# Sheet2.net
KiCad netlist of a schematic drawn in Altium Designer
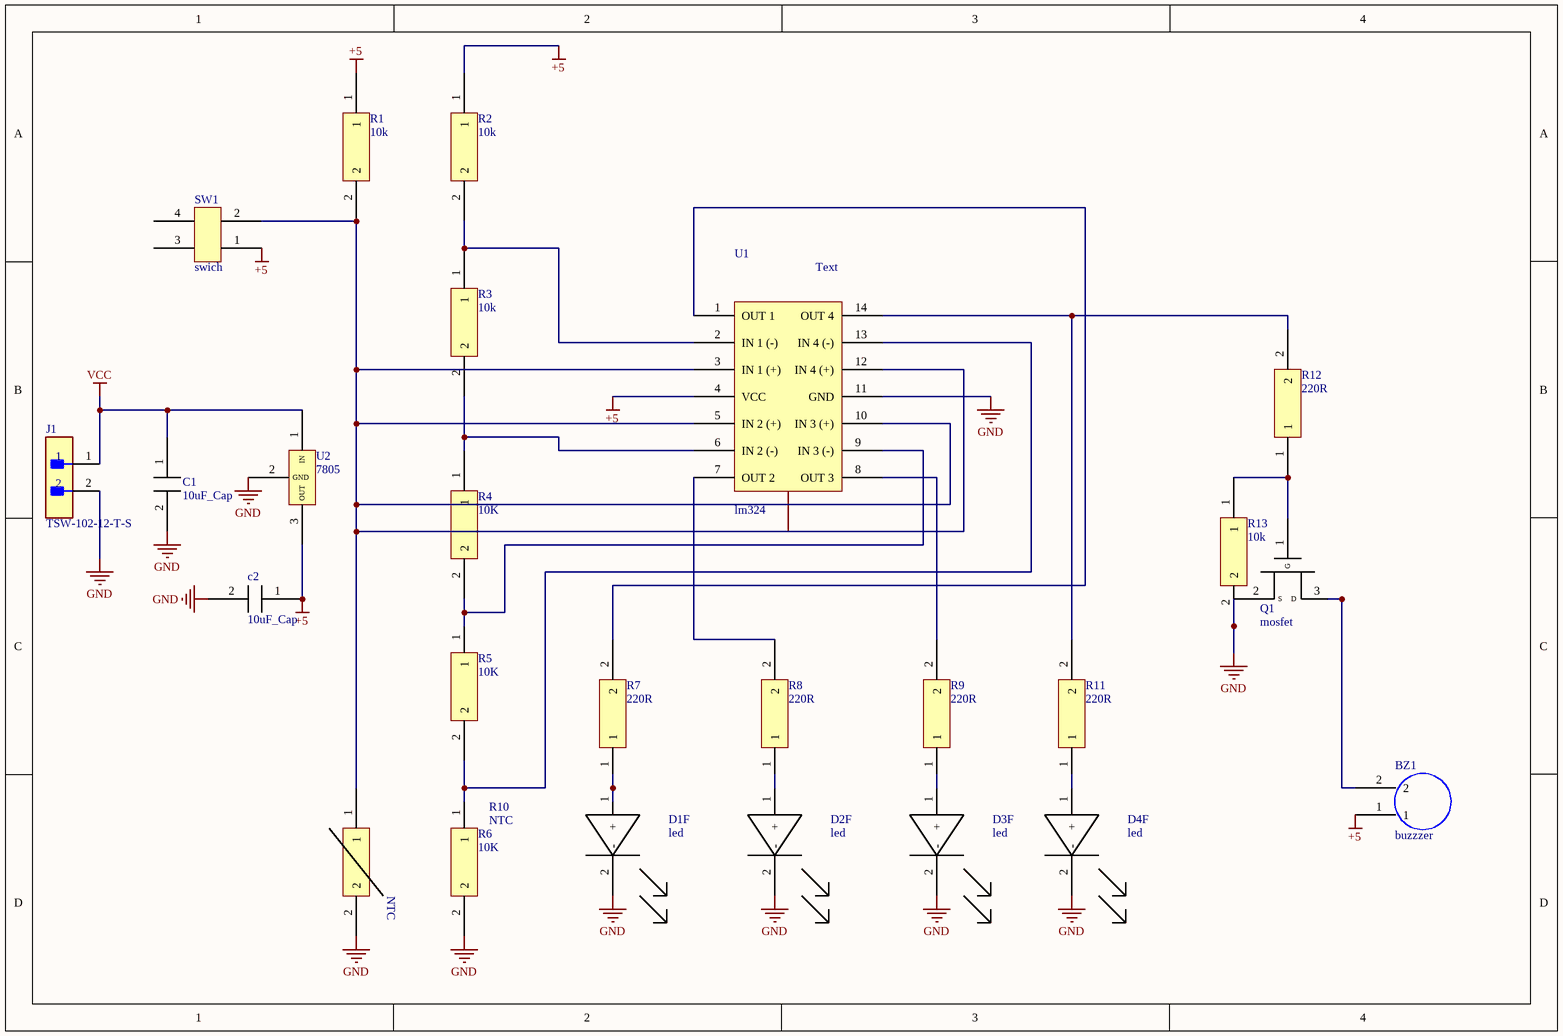
[diagram p0: Sheet2.SchDoc]

(export (version "E")
  (design (tool "Eeschema 10.0.6"))
  (components
    (comp (ref "BZ1")
      (value "buzzzer")
      (footprint "PCBComponent_1")
      (libsource (lib "Schlib1") (part "buzzzer"))
    )
    (comp (ref "C1")
      (value "10uF_Cap")
      (footprint "CAPCP2012X14N")
      (libsource (lib "Schlib1") (part "10uF_Cap"))
    )
    (comp (ref "c2")
      (value "10uF_Cap")
      (footprint "DIOC2012X06N")
      (libsource (lib "Schlib1") (part "10uF_Cap"))
    )
    (comp (ref "D1") (value "led") (footprint "DIOC2012X06") (libsource (lib "Schlib1") (part "led")))
    (comp (ref "D2") (value "led") (footprint "DIOC2012X06N") (libsource (lib "Schlib1") (part "led")))
    (comp (ref "D3") (value "led") (footprint "DIOC2012X06N") (libsource (lib "Schlib1") (part "led")))
    (comp (ref "D4") (value "led") (footprint "DIOC2012X06N") (libsource (lib "Schlib1") (part "led")))
    (comp (ref "J1")
      (value "TSW-102-12-T-S")
      (footprint "FP-TSW-102-12-T-S-MFG")
      (description "CONN HEADER VERT 2POS 2.54MM")
      (libsource (lib "Altium Content Vault") (part "3bc925449376181038e59eaffc5286c"))
    )
    (comp (ref "Q1")
      (value "mosfet")
      (footprint "SOT95P245X110-3N")
      (libsource (lib "Schlib1") (part "mosfet"))
    )
    (comp (ref "R1")
      (value "10k")
      (footprint "CAPCP2012X14N")
      (description "RES_0805")
      (libsource (lib "Schlib1") (part "RES_0805"))
    )
    (comp (ref "R2")
      (value "10k")
      (footprint "CAPCP2012X14N")
      (description "RES_0805")
      (libsource (lib "Schlib1") (part "RES_0805"))
    )
    (comp (ref "R3")
      (value "10k")
      (footprint "CAPCP2012X14N")
      (description "RES_0805")
      (libsource (lib "Schlib1") (part "RES_0805"))
    )
    (comp (ref "R4")
      (value "10K")
      (footprint "CAPCP2012X14N")
      (description "RES_0805")
      (libsource (lib "Schlib1") (part "RES_0805"))
    )
    (comp (ref "R5")
      (value "10K")
      (footprint "CAPCP2012X14N")
      (description "RES_0805")
      (libsource (lib "Schlib1") (part "RES_0805"))
    )
    (comp (ref "R6")
      (value "10K")
      (footprint "CAPCP2012X14N")
      (description "RES_0805")
      (libsource (lib "Schlib1") (part "RES_0805"))
    )
    (comp (ref "R7")
      (value "220R")
      (footprint "CAPCP2012X14N")
      (description "RES_0805")
      (libsource (lib "") (part "RES_0805_1"))
    )
    (comp (ref "R8")
      (value "220R")
      (footprint "CAPCP2012X14N")
      (description "RES_0805")
      (libsource (lib "") (part "RES_0805_1"))
    )
    (comp (ref "R9")
      (value "220R")
      (footprint "CAPCP2012X14N")
      (description "RES_0805")
      (libsource (lib "") (part "RES_0805_1"))
    )
    (comp (ref "R10") (value "NTC") (footprint "NTC") (libsource (lib "Schlib1") (part "NTC")))
    (comp (ref "R11")
      (value "220R")
      (footprint "CAPCP2012X14N")
      (description "RES_0805")
      (libsource (lib "") (part "RES_0805_1"))
    )
    (comp (ref "R12")
      (value "220R")
      (footprint "RESC2012X06N")
      (description "RES_0805")
      (libsource (lib "") (part "RES_0805_1"))
    )
    (comp (ref "R13")
      (value "10k")
      (footprint "RESC2012X06N")
      (description "RES_0805")
      (libsource (lib "Schlib1") (part "RES_0805"))
    )
    (comp (ref "SW1")
      (value "swich")
      (footprint "PCBComponent_1 - duplicate4")
      (libsource (lib "Schlib1") (part "swich"))
    )
    (comp (ref "U1")
      (value "lm324")
      (footprint "SOIC127P600X175-14N")
      (libsource (lib "Schlib1") (part "lm324"))
    )
    (comp (ref "U2")
      (value "7805")
      (footprint "DPAK228P990X238-3N")
      (libsource (lib "Schlib1") (part "7805"))
    )
  )
  (nets
    (net (code "1") (name "+5") (class "Default")
      (node (ref "BZ1") (pin "1") (pinfunction "1_1") (pintype "passive"))
      (node (ref "R1") (pin "1") (pinfunction "1_1") (pintype "passive"))
      (node (ref "R2") (pin "1") (pinfunction "1_1") (pintype "passive"))
      (node (ref "SW1") (pin "1") (pintype "passive"))
      (node (ref "U1") (pin "4") (pinfunction "VCC_4") (pintype "passive"))
      (node (ref "U2") (pin "3") (pinfunction "OUT_3") (pintype "passive"))
      (node (ref "c2") (pin "1") (pintype "passive"))
    )
    (net (code "2") (name "GND") (class "Default")
      (node (ref "C1") (pin "2") (pintype "passive"))
      (node (ref "D1") (pin "2") (pinfunction "-_2") (pintype "passive"))
      (node (ref "D2") (pin "2") (pinfunction "-_2") (pintype "passive"))
      (node (ref "D3") (pin "2") (pinfunction "-_2") (pintype "passive"))
      (node (ref "D4") (pin "2") (pinfunction "-_2") (pintype "passive"))
      (node (ref "J1") (pin "2") (pinfunction "2_2") (pintype "passive"))
      (node (ref "Q1") (pin "2") (pinfunction "S_2") (pintype "passive"))
      (node (ref "R10") (pin "2") (pinfunction "2_2") (pintype "passive"))
      (node (ref "R13") (pin "2") (pinfunction "2_2") (pintype "passive"))
      (node (ref "R6") (pin "2") (pinfunction "2_2") (pintype "passive"))
      (node (ref "U1") (pin "11") (pinfunction "GND_11") (pintype "passive"))
      (node (ref "U2") (pin "2") (pinfunction "GND_2") (pintype "passive"))
      (node (ref "c2") (pin "2") (pintype "passive"))
    )
    (net (code "3") (name "Net-(D1F-+)") (class "Default")
      (node (ref "D1") (pin "1") (pinfunction "+_1") (pintype "passive"))
      (node (ref "R7") (pin "1") (pinfunction "1_1") (pintype "passive"))
    )
    (net (code "4") (name "Net-(D2F-+)") (class "Default")
      (node (ref "D2") (pin "1") (pinfunction "+_1") (pintype "passive"))
      (node (ref "R8") (pin "1") (pinfunction "1_1") (pintype "passive"))
    )
    (net (code "5") (name "Net-(D3F-+)") (class "Default")
      (node (ref "D3") (pin "1") (pinfunction "+_1") (pintype "passive"))
      (node (ref "R9") (pin "1") (pinfunction "1_1") (pintype "passive"))
    )
    (net (code "6") (name "Net-(D4F-+)") (class "Default")
      (node (ref "D4") (pin "1") (pinfunction "+_1") (pintype "passive"))
      (node (ref "R11") (pin "1") (pinfunction "1_1") (pintype "passive"))
    )
    (net (code "7") (name "Net-(Q1-D)") (class "Default")
      (node (ref "BZ1") (pin "2") (pinfunction "2_2") (pintype "passive"))
      (node (ref "Q1") (pin "3") (pinfunction "D_3") (pintype "passive"))
    )
    (net (code "8") (name "Net-(Q1-G)") (class "Default")
      (node (ref "Q1") (pin "1") (pinfunction "G_1") (pintype "passive"))
      (node (ref "R12") (pin "1") (pinfunction "1_1") (pintype "passive"))
      (node (ref "R13") (pin "1") (pinfunction "1_1") (pintype "passive"))
    )
    (net (code "9") (name "Net-(U1-IN_1_(+))") (class "Default")
      (node (ref "R1") (pin "2") (pinfunction "2_2") (pintype "passive"))
      (node (ref "R10") (pin "1") (pinfunction "1_1") (pintype "passive"))
      (node (ref "SW1") (pin "2") (pintype "passive"))
      (node (ref "U1") (pin "10") (pinfunction "IN_3_(+)_10") (pintype "passive"))
      (node (ref "U1") (pin "12") (pinfunction "IN_4_(+)_12") (pintype "passive"))
      (node (ref "U1") (pin "3") (pinfunction "IN_1_(+)_3") (pintype "passive"))
      (node (ref "U1") (pin "5") (pinfunction "IN_2_(+)_5") (pintype "passive"))
    )
    (net (code "10") (name "Net-(U1-IN_1_(-))") (class "Default")
      (node (ref "R2") (pin "2") (pinfunction "2_2") (pintype "passive"))
      (node (ref "R3") (pin "1") (pinfunction "1_1") (pintype "passive"))
      (node (ref "U1") (pin "2") (pinfunction "IN_1_(-)_2") (pintype "passive"))
    )
    (net (code "11") (name "Net-(U1-IN_2_(-))") (class "Default")
      (node (ref "R3") (pin "2") (pinfunction "2_2") (pintype "passive"))
      (node (ref "R4") (pin "1") (pinfunction "1_1") (pintype "passive"))
      (node (ref "U1") (pin "6") (pinfunction "IN_2_(-)_6") (pintype "passive"))
    )
    (net (code "12") (name "Net-(U1-IN_3_(-))") (class "Default")
      (node (ref "R4") (pin "2") (pinfunction "2_2") (pintype "passive"))
      (node (ref "R5") (pin "1") (pinfunction "1_1") (pintype "passive"))
      (node (ref "U1") (pin "9") (pinfunction "IN_3_(-)_9") (pintype "passive"))
    )
    (net (code "13") (name "Net-(U1-IN_4_(-))") (class "Default")
      (node (ref "R5") (pin "2") (pinfunction "2_2") (pintype "passive"))
      (node (ref "R6") (pin "1") (pinfunction "1_1") (pintype "passive"))
      (node (ref "U1") (pin "13") (pinfunction "IN_4_(-)_13") (pintype "passive"))
    )
    (net (code "14") (name "Net-(U1-OUT_1)") (class "Default")
      (node (ref "R7") (pin "2") (pinfunction "2_2") (pintype "passive"))
      (node (ref "U1") (pin "1") (pinfunction "OUT_1_1") (pintype "passive"))
    )
    (net (code "15") (name "Net-(U1-OUT_2)") (class "Default")
      (node (ref "R8") (pin "2") (pinfunction "2_2") (pintype "passive"))
      (node (ref "U1") (pin "7") (pinfunction "OUT_2_7") (pintype "passive"))
    )
    (net (code "16") (name "Net-(U1-OUT_3)") (class "Default")
      (node (ref "R9") (pin "2") (pinfunction "2_2") (pintype "passive"))
      (node (ref "U1") (pin "8") (pinfunction "OUT_3_8") (pintype "passive"))
    )
    (net (code "17") (name "Net-(U1-OUT_4)") (class "Default")
      (node (ref "R11") (pin "2") (pinfunction "2_2") (pintype "passive"))
      (node (ref "R12") (pin "2") (pinfunction "2_2") (pintype "passive"))
      (node (ref "U1") (pin "14") (pinfunction "OUT_4_14") (pintype "passive"))
    )
    (net (code "18") (name "VCC") (class "Default")
      (node (ref "C1") (pin "1") (pintype "passive"))
      (node (ref "J1") (pin "1") (pinfunction "1_1") (pintype "passive"))
      (node (ref "U2") (pin "1") (pinfunction "IN_1") (pintype "passive"))
    )
    (net (code "19") (name "unconnected-(SW1-Pad3)") (class "Default")
      (node (ref "SW1") (pin "3") (pintype "passive"))
    )
    (net (code "20") (name "unconnected-(SW1-Pad4)") (class "Default")
      (node (ref "SW1") (pin "4") (pintype "passive"))
    )
  )
)
